# photon_v019.net
KiCad netlist of a schematic drawn in EAGLE
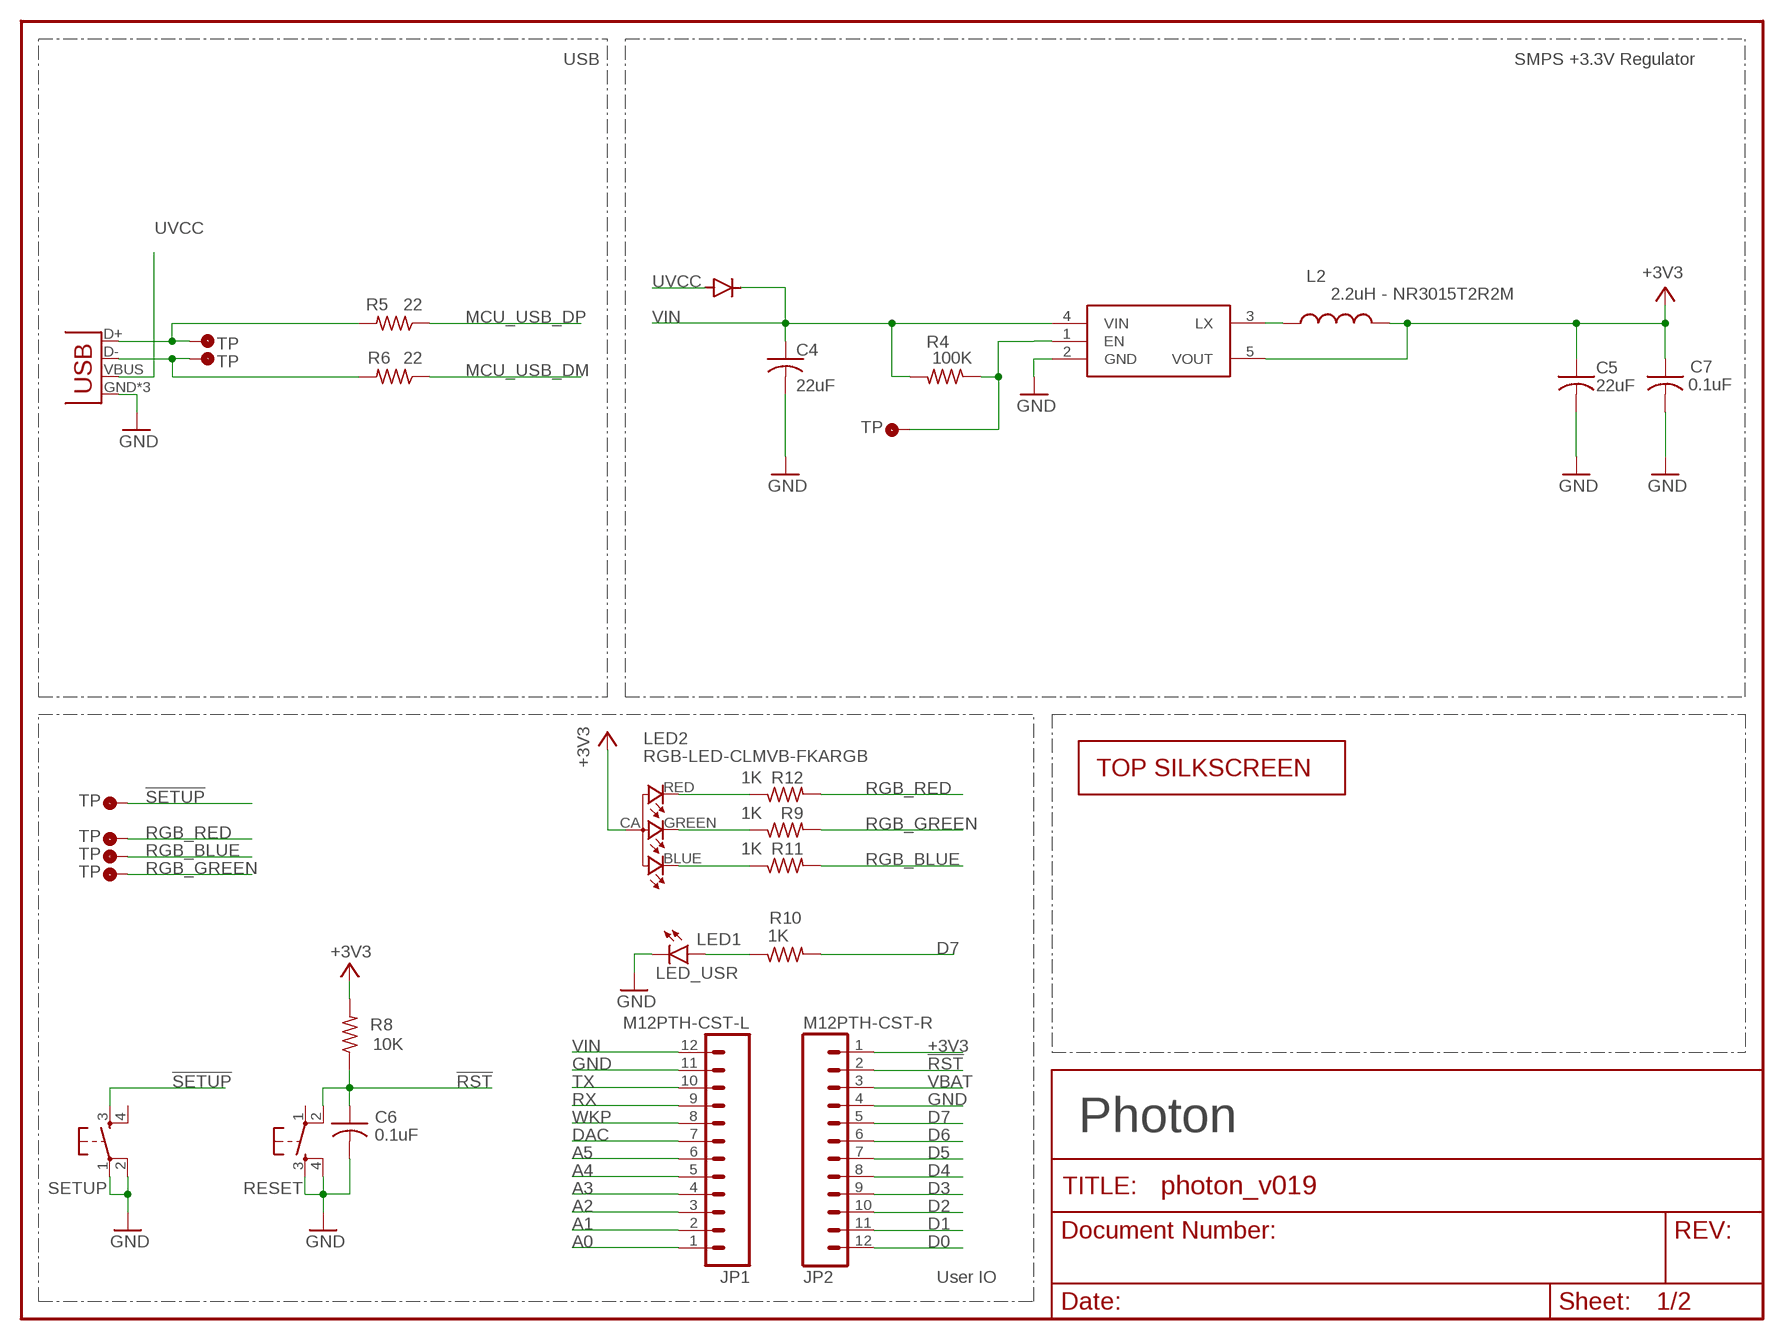
[diagram p0: schematic, sheet 1]
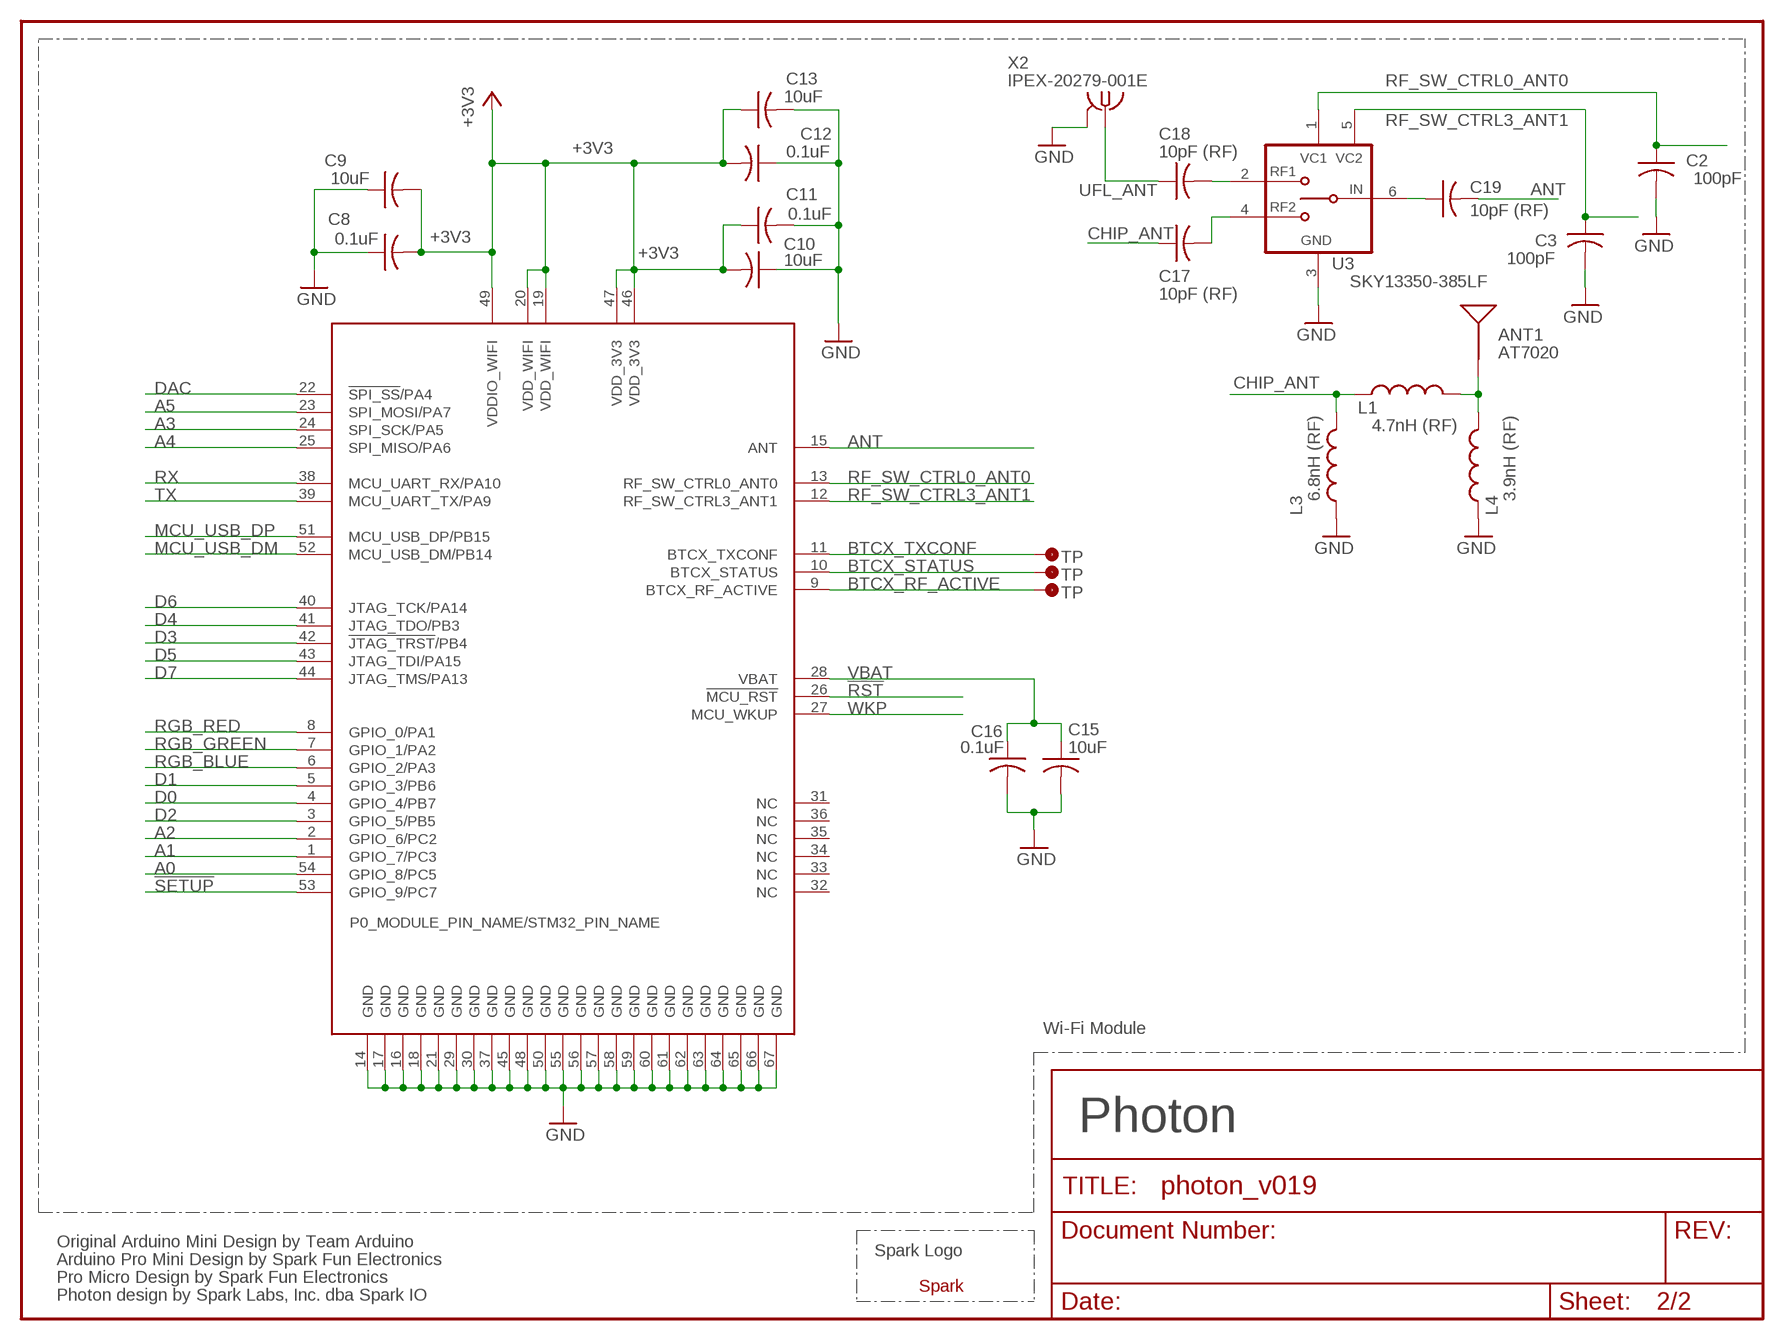
[diagram p1: schematic, sheet 2]

(export (version "E")
  (design (tool "Eeschema 10.0.6"))
  (components
    (comp (ref "C4")
      (value "22uF")
      (footprint "eagle-import:C0603_B")
      (libsource (lib "eagle-import") (part "C-US0603"))
    )
    (comp (ref "C5")
      (value "22uF")
      (footprint "eagle-import:C0603_B")
      (libsource (lib "eagle-import") (part "C-US0603"))
    )
    (comp (ref "C6")
      (value "0.1uF")
      (footprint "eagle-import:C0402_B")
      (libsource (lib "eagle-import") (part "C-US"))
    )
    (comp (ref "C7")
      (value "0.1uF")
      (footprint "eagle-import:C0402_B")
      (libsource (lib "eagle-import") (part "C-US"))
    )
    (comp (ref "D1")
      (value "DIODE")
      (footprint "eagle-import:DIODE-DO-220AA(SMP)")
      (libsource (lib "eagle-import") (part "DIODE"))
    )
    (comp (ref "JP1")
      (value "M12PTH-CST-L")
      (footprint "eagle-import:1X12-CASTELLATED")
      (libsource (lib "eagle-import") (part "M12PTH-CST-L"))
    )
    (comp (ref "JP2")
      (value "M12PTH-CST-R")
      (footprint "eagle-import:1X12-CASTELLATED")
      (libsource (lib "eagle-import") (part "M12PTH-CST-R"))
    )
    (comp (ref "L2")
      (value "2.2uH - NR3015T2R2M")
      (footprint "eagle-import:INDUCTOR-NR3015")
      (libsource (lib "eagle-import") (part "INDUCTORB"))
    )
    (comp (ref "LED2")
      (value "RGB-LED-CLMVB-FKARGB")
      (footprint "eagle-import:PLCC4-2MM-RGB")
      (libsource (lib "eagle-import") (part "RGB-LED-CLMVB-FKARGB"))
    )
    (comp (ref "LED_USR")
      (value "LED-0603-NO-SS")
      (footprint "eagle-import:LED-0603-NO-SS")
      (libsource (lib "eagle-import") (part "LED-0603-NO-SS"))
    )
    (comp (ref "R4")
      (value "100K")
      (footprint "eagle-import:R0402_B")
      (libsource (lib "eagle-import") (part "R-US_"))
    )
    (comp (ref "R5")
      (value "22")
      (footprint "eagle-import:R0402_B")
      (libsource (lib "eagle-import") (part "R-US_"))
    )
    (comp (ref "R6")
      (value "22")
      (footprint "eagle-import:R0402_B")
      (libsource (lib "eagle-import") (part "R-US_"))
    )
    (comp (ref "R8")
      (value "10K")
      (footprint "eagle-import:R0402_B")
      (libsource (lib "eagle-import") (part "R-US_"))
    )
    (comp (ref "R9")
      (value "1K")
      (footprint "eagle-import:R0402_B")
      (libsource (lib "eagle-import") (part "R-US_"))
    )
    (comp (ref "R10")
      (value "1K")
      (footprint "eagle-import:R0402_B")
      (libsource (lib "eagle-import") (part "R-US_"))
    )
    (comp (ref "R11")
      (value "1K")
      (footprint "eagle-import:R0402_B")
      (libsource (lib "eagle-import") (part "R-US_"))
    )
    (comp (ref "R12")
      (value "1K")
      (footprint "eagle-import:R0402_B")
      (libsource (lib "eagle-import") (part "R-US_"))
    )
    (comp (ref "RESET")
      (value "KMR211GLFS")
      (footprint "eagle-import:TACTILE_SWITCH_SMD")
      (libsource (lib "eagle-import") (part "TAC_SWITCHSMD"))
    )
    (comp (ref "SETUP")
      (value "KMR211GLFS")
      (footprint "eagle-import:TACTILE_SWITCH_SMD")
      (libsource (lib "eagle-import") (part "TAC_SWITCHSMD"))
    )
    (comp (ref "U$1")
      (value "PHOTON-TOP-SS2")
      (footprint "eagle-import:PHOTON-TOP-SS-2")
      (libsource (lib "eagle-import") (part "PHOTON-TOP-SS2"))
    )
    (comp (ref "U$3")
      (value "TP3")
      (footprint "eagle-import:TP60_BOT")
      (libsource (lib "eagle-import") (part "TP3"))
    )
    (comp (ref "U$5")
      (value "TP1")
      (footprint "eagle-import:TP35_BOT")
      (libsource (lib "eagle-import") (part "TP1"))
    )
    (comp (ref "U$6")
      (value "TP1")
      (footprint "eagle-import:TP35_BOT")
      (libsource (lib "eagle-import") (part "TP1"))
    )
    (comp (ref "U$7")
      (value "TP1")
      (footprint "eagle-import:TP35_BOT")
      (libsource (lib "eagle-import") (part "TP1"))
    )
    (comp (ref "U$11")
      (value "R8008-33")
      (footprint "eagle-import:SOT23-5")
      (libsource (lib "eagle-import") (part "R8008-33"))
    )
    (comp (ref "U$12")
      (value "TP3")
      (footprint "eagle-import:TP60_BOT")
      (libsource (lib "eagle-import") (part "TP3"))
    )
    (comp (ref "U$13")
      (value "TP3")
      (footprint "eagle-import:TP60_BOT")
      (libsource (lib "eagle-import") (part "TP3"))
    )
    (comp (ref "U$14")
      (value "TP3")
      (footprint "eagle-import:TP60_BOT")
      (libsource (lib "eagle-import") (part "TP3"))
    )
    (comp (ref "X1")
      (value "USB-MICROB")
      (footprint "eagle-import:USB-MICROB-SLOT-HOLE")
      (libsource (lib "eagle-import") (part "USBUSB-MICROB-SLOT-HOLE"))
    )
    (comp (ref "ANT1")
      (value "AT7020")
      (footprint "eagle-import:AT7020")
      (libsource (lib "eagle-import") (part "AT7020"))
    )
    (comp (ref "C2")
      (value "100pF")
      (footprint "eagle-import:C0402_B")
      (libsource (lib "eagle-import") (part "C-US"))
    )
    (comp (ref "C3")
      (value "100pF")
      (footprint "eagle-import:C0402_B")
      (libsource (lib "eagle-import") (part "C-US"))
    )
    (comp (ref "C8")
      (value "0.1uF")
      (footprint "eagle-import:C0402_B")
      (libsource (lib "eagle-import") (part "C-US"))
    )
    (comp (ref "C9")
      (value "10uF")
      (footprint "eagle-import:C0603_B")
      (libsource (lib "eagle-import") (part "C-US0603"))
    )
    (comp (ref "C10")
      (value "10uF")
      (footprint "eagle-import:C0603_B")
      (libsource (lib "eagle-import") (part "C-US0603"))
    )
    (comp (ref "C11")
      (value "0.1uF")
      (footprint "eagle-import:C0402_B")
      (libsource (lib "eagle-import") (part "C-US"))
    )
    (comp (ref "C12")
      (value "0.1uF")
      (footprint "eagle-import:C0402_B")
      (libsource (lib "eagle-import") (part "C-US"))
    )
    (comp (ref "C13")
      (value "10uF")
      (footprint "eagle-import:C0603_B")
      (libsource (lib "eagle-import") (part "C-US0603"))
    )
    (comp (ref "C15")
      (value "10uF")
      (footprint "eagle-import:C0603_B")
      (libsource (lib "eagle-import") (part "C-US0603"))
    )
    (comp (ref "C16")
      (value "0.1uF")
      (footprint "eagle-import:C0402_B")
      (libsource (lib "eagle-import") (part "C-US"))
    )
    (comp (ref "C17")
      (value "10pF (RF)")
      (footprint "eagle-import:C0201_B")
      (libsource (lib "eagle-import") (part "C-US0201"))
    )
    (comp (ref "C18")
      (value "10pF (RF)")
      (footprint "eagle-import:C0201_B")
      (libsource (lib "eagle-import") (part "C-US0201"))
    )
    (comp (ref "C19")
      (value "10pF (RF)")
      (footprint "eagle-import:C0201_B")
      (libsource (lib "eagle-import") (part "C-US0201"))
    )
    (comp (ref "L1")
      (value "4.7nH (RF)")
      (footprint "eagle-import:L0402_B")
      (libsource (lib "eagle-import") (part "INDUCTOR"))
    )
    (comp (ref "L3")
      (value "6.8nH (RF)")
      (footprint "eagle-import:L0402_B")
      (libsource (lib "eagle-import") (part "INDUCTOR"))
    )
    (comp (ref "L4")
      (value "3.9nH (RF)")
      (footprint "eagle-import:L0402_B")
      (libsource (lib "eagle-import") (part "INDUCTOR"))
    )
    (comp (ref "U$2")
      (value "SPARK_LOGO2")
      (footprint "eagle-import:SPARK_LOGO2")
      (libsource (lib "eagle-import") (part "SPARK_LOGO2"))
    )
    (comp (ref "U$8")
      (value "TP1")
      (footprint "eagle-import:TP35_BOT")
      (libsource (lib "eagle-import") (part "TP1"))
    )
    (comp (ref "U$9")
      (value "TP1")
      (footprint "eagle-import:TP35_BOT")
      (libsource (lib "eagle-import") (part "TP1"))
    )
    (comp (ref "U$10")
      (value "TP1")
      (footprint "eagle-import:TP35_BOT")
      (libsource (lib "eagle-import") (part "TP1"))
    )
    (comp (ref "U1")
      (value "WM-N-BM-09")
      (footprint "eagle-import:WM-N-BM-09")
      (libsource (lib "eagle-import") (part "WM-N-BM-09"))
    )
    (comp (ref "U3")
      (value "SKY13350-385LF")
      (footprint "eagle-import:XFDFN-6")
      (libsource (lib "eagle-import") (part "SKY13350-385LF"))
    )
    (comp (ref "X2")
      (value "IPEX-20279-001E")
      (footprint "eagle-import:IPEX-20279-001E")
      (libsource (lib "eagle-import") (part "IPEX-20279-001E"))
    )
  )
  (nets
    (net (code "1") (name "+3V3") (class "Default")
      (node (ref "C10") (pin "2") (pinfunction "2_2") (pintype "passive"))
      (node (ref "C11") (pin "1") (pinfunction "1_1") (pintype "passive"))
      (node (ref "C12") (pin "2") (pinfunction "2_2") (pintype "passive"))
      (node (ref "C13") (pin "1") (pinfunction "1_1") (pintype "passive"))
      (node (ref "C5") (pin "1") (pinfunction "1_1") (pintype "passive"))
      (node (ref "C7") (pin "1") (pinfunction "1_1") (pintype "passive"))
      (node (ref "C8") (pin "2") (pinfunction "2_2") (pintype "passive"))
      (node (ref "C9") (pin "2") (pinfunction "2_2") (pintype "passive"))
      (node (ref "JP2") (pin "1") (pinfunction "1_1") (pintype "passive"))
      (node (ref "L2") (pin "2") (pinfunction "2_2") (pintype "passive"))
      (node (ref "LED2") (pin "CA") (pinfunction "1_CA") (pintype "passive"))
      (node (ref "R8") (pin "2") (pinfunction "2_2") (pintype "passive"))
      (node (ref "U$11") (pin "5") (pinfunction "VOUT_5") (pintype "bidirectional"))
      (node (ref "U1") (pin "19") (pinfunction "VDD_WIFI_19") (pintype "bidirectional"))
      (node (ref "U1") (pin "20") (pinfunction "VDD_WIFI_20") (pintype "bidirectional"))
      (node (ref "U1") (pin "46") (pinfunction "VDD_3V3_46") (pintype "bidirectional"))
      (node (ref "U1") (pin "47") (pinfunction "VDD_3V3_47") (pintype "bidirectional"))
      (node (ref "U1") (pin "49") (pinfunction "VDDIO_WIFI_49") (pintype "bidirectional"))
    )
    (net (code "2") (name "A0") (class "Default")
      (node (ref "JP1") (pin "1") (pinfunction "12_1") (pintype "passive"))
      (node (ref "U1") (pin "54") (pinfunction "GPIO_8/PC5_54") (pintype "bidirectional"))
    )
    (net (code "3") (name "A1") (class "Default")
      (node (ref "JP1") (pin "2") (pinfunction "11_2") (pintype "passive"))
      (node (ref "U1") (pin "1") (pinfunction "GPIO_7/PC3_1") (pintype "bidirectional"))
    )
    (net (code "4") (name "A2") (class "Default")
      (node (ref "JP1") (pin "3") (pinfunction "10_3") (pintype "passive"))
      (node (ref "U1") (pin "2") (pinfunction "GPIO_6/PC2_2") (pintype "bidirectional"))
    )
    (net (code "5") (name "A3") (class "Default")
      (node (ref "JP1") (pin "4") (pinfunction "9_4") (pintype "passive"))
      (node (ref "U1") (pin "24") (pinfunction "SPI_SCK/PA5_24") (pintype "bidirectional"))
    )
    (net (code "6") (name "A4") (class "Default")
      (node (ref "JP1") (pin "5") (pinfunction "8_5") (pintype "passive"))
      (node (ref "U1") (pin "25") (pinfunction "SPI_MISO/PA6_25") (pintype "bidirectional"))
    )
    (net (code "7") (name "A5") (class "Default")
      (node (ref "JP1") (pin "6") (pinfunction "7_6") (pintype "passive"))
      (node (ref "U1") (pin "23") (pinfunction "SPI_MOSI/PA7_23") (pintype "bidirectional"))
    )
    (net (code "8") (name "ANT") (class "Default")
      (node (ref "C19") (pin "2") (pinfunction "2_2") (pintype "passive"))
      (node (ref "U1") (pin "15") (pinfunction "ANT_15") (pintype "bidirectional"))
    )
    (net (code "9") (name "BTCX_RF_ACTIVE") (class "Default")
      (node (ref "U$10") (pin "P$1") (pinfunction "TP_P$1") (pintype "bidirectional"))
      (node (ref "U1") (pin "9") (pinfunction "BTCX_RF_ACTIVE_9") (pintype "bidirectional"))
    )
    (net (code "10") (name "BTCX_STATUS") (class "Default")
      (node (ref "U$9") (pin "P$1") (pinfunction "TP_P$1") (pintype "bidirectional"))
      (node (ref "U1") (pin "10") (pinfunction "BTCX_STATUS_10") (pintype "bidirectional"))
    )
    (net (code "11") (name "BTCX_TXCONF") (class "Default")
      (node (ref "U$8") (pin "P$1") (pinfunction "TP_P$1") (pintype "bidirectional"))
      (node (ref "U1") (pin "11") (pinfunction "BTCX_TXCONF_11") (pintype "bidirectional"))
    )
    (net (code "12") (name "CHIP_ANT") (class "Default")
      (node (ref "C17") (pin "1") (pinfunction "1_1") (pintype "passive"))
      (node (ref "L1") (pin "1") (pinfunction "1_1") (pintype "passive"))
      (node (ref "L3") (pin "2") (pinfunction "2_2") (pintype "passive"))
    )
    (net (code "13") (name "D0") (class "Default")
      (node (ref "JP2") (pin "12") (pinfunction "12_12") (pintype "passive"))
      (node (ref "U1") (pin "4") (pinfunction "GPIO_4/PB7_4") (pintype "bidirectional"))
    )
    (net (code "14") (name "D1") (class "Default")
      (node (ref "JP2") (pin "11") (pinfunction "11_11") (pintype "passive"))
      (node (ref "U1") (pin "5") (pinfunction "GPIO_3/PB6_5") (pintype "bidirectional"))
    )
    (net (code "15") (name "D2") (class "Default")
      (node (ref "JP2") (pin "10") (pinfunction "10_10") (pintype "passive"))
      (node (ref "U1") (pin "3") (pinfunction "GPIO_5/PB5_3") (pintype "bidirectional"))
    )
    (net (code "16") (name "D3") (class "Default")
      (node (ref "JP2") (pin "9") (pinfunction "9_9") (pintype "passive"))
      (node (ref "U1") (pin "42") (pinfunction "~{JTAG_TRST}/PB4_42") (pintype "bidirectional"))
    )
    (net (code "17") (name "D4") (class "Default")
      (node (ref "JP2") (pin "8") (pinfunction "8_8") (pintype "passive"))
      (node (ref "U1") (pin "41") (pinfunction "JTAG_TDO/PB3_41") (pintype "bidirectional"))
    )
    (net (code "18") (name "D5") (class "Default")
      (node (ref "JP2") (pin "7") (pinfunction "7_7") (pintype "passive"))
      (node (ref "U1") (pin "43") (pinfunction "JTAG_TDI/PA15_43") (pintype "bidirectional"))
    )
    (net (code "19") (name "D6") (class "Default")
      (node (ref "JP2") (pin "6") (pinfunction "6_6") (pintype "passive"))
      (node (ref "U1") (pin "40") (pinfunction "JTAG_TCK/PA14_40") (pintype "bidirectional"))
    )
    (net (code "20") (name "D7") (class "Default")
      (node (ref "JP2") (pin "5") (pinfunction "5_5") (pintype "passive"))
      (node (ref "R10") (pin "2") (pinfunction "2_2") (pintype "passive"))
      (node (ref "U1") (pin "44") (pinfunction "JTAG_TMS/PA13_44") (pintype "bidirectional"))
    )
    (net (code "21") (name "DAC") (class "Default")
      (node (ref "JP1") (pin "7") (pinfunction "6_7") (pintype "passive"))
      (node (ref "U1") (pin "22") (pinfunction "~{SPI_SS}/PA4_22") (pintype "bidirectional"))
    )
    (net (code "22") (name "GND") (class "Default")
      (node (ref "C10") (pin "1") (pinfunction "1_1") (pintype "passive"))
      (node (ref "C11") (pin "2") (pinfunction "2_2") (pintype "passive"))
      (node (ref "C12") (pin "1") (pinfunction "1_1") (pintype "passive"))
      (node (ref "C13") (pin "2") (pinfunction "2_2") (pintype "passive"))
      (node (ref "C15") (pin "2") (pinfunction "2_2") (pintype "passive"))
      (node (ref "C16") (pin "2") (pinfunction "2_2") (pintype "passive"))
      (node (ref "C2") (pin "2") (pinfunction "2_2") (pintype "passive"))
      (node (ref "C3") (pin "2") (pinfunction "2_2") (pintype "passive"))
      (node (ref "C4") (pin "2") (pinfunction "2_2") (pintype "passive"))
      (node (ref "C5") (pin "2") (pinfunction "2_2") (pintype "passive"))
      (node (ref "C6") (pin "2") (pinfunction "2_2") (pintype "passive"))
      (node (ref "C7") (pin "2") (pinfunction "2_2") (pintype "passive"))
      (node (ref "C8") (pin "1") (pinfunction "1_1") (pintype "passive"))
      (node (ref "C9") (pin "1") (pinfunction "1_1") (pintype "passive"))
      (node (ref "JP1") (pin "11") (pinfunction "2_11") (pintype "passive"))
      (node (ref "JP2") (pin "4") (pinfunction "4_4") (pintype "passive"))
      (node (ref "L3") (pin "1") (pinfunction "1_1") (pintype "passive"))
      (node (ref "L4") (pin "1") (pinfunction "1_1") (pintype "passive"))
      (node (ref "LED_USR") (pin "C1") (pinfunction "C_C1") (pintype "passive"))
      (node (ref "RESET") (pin "3") (pinfunction "3_3") (pintype "passive"))
      (node (ref "RESET") (pin "4") (pinfunction "4_4") (pintype "passive"))
      (node (ref "SETUP") (pin "1") (pinfunction "1_1") (pintype "passive"))
      (node (ref "SETUP") (pin "2") (pinfunction "2_2") (pintype "passive"))
      (node (ref "U$11") (pin "2") (pinfunction "GND_2") (pintype "bidirectional"))
      (node (ref "U1") (pin "14") (pinfunction "GND_14") (pintype "bidirectional"))
      (node (ref "U1") (pin "16") (pinfunction "GND_16") (pintype "bidirectional"))
      (node (ref "U1") (pin "17") (pinfunction "GND_17") (pintype "bidirectional"))
      (node (ref "U1") (pin "18") (pinfunction "GND_18") (pintype "bidirectional"))
      (node (ref "U1") (pin "21") (pinfunction "GND_21") (pintype "bidirectional"))
      (node (ref "U1") (pin "29") (pinfunction "GND_29") (pintype "bidirectional"))
      (node (ref "U1") (pin "30") (pinfunction "GND_30") (pintype "bidirectional"))
      (node (ref "U1") (pin "37") (pinfunction "GND_37") (pintype "bidirectional"))
      (node (ref "U1") (pin "45") (pinfunction "GND_45") (pintype "bidirectional"))
      (node (ref "U1") (pin "48") (pinfunction "GND_48") (pintype "bidirectional"))
      (node (ref "U1") (pin "50") (pinfunction "GND_50") (pintype "bidirectional"))
      (node (ref "U1") (pin "55") (pinfunction "GND_55") (pintype "bidirectional"))
      (node (ref "U1") (pin "56") (pinfunction "GND_56") (pintype "bidirectional"))
      (node (ref "U1") (pin "57") (pinfunction "GND_57") (pintype "bidirectional"))
      (node (ref "U1") (pin "58") (pinfunction "GND_58") (pintype "bidirectional"))
      (node (ref "U1") (pin "59") (pinfunction "GND_59") (pintype "bidirectional"))
      (node (ref "U1") (pin "60") (pinfunction "GND_60") (pintype "bidirectional"))
      (node (ref "U1") (pin "61") (pinfunction "GND_61") (pintype "bidirectional"))
      (node (ref "U1") (pin "62") (pinfunction "GND_62") (pintype "bidirectional"))
      (node (ref "U1") (pin "63") (pinfunction "GND_63") (pintype "bidirectional"))
      (node (ref "U1") (pin "64") (pinfunction "GND_64") (pintype "bidirectional"))
      (node (ref "U1") (pin "65") (pinfunction "GND_65") (pintype "bidirectional"))
      (node (ref "U1") (pin "66") (pinfunction "GND_66") (pintype "bidirectional"))
      (node (ref "U1") (pin "67") (pinfunction "GND_67") (pintype "bidirectional"))
      (node (ref "U3") (pin "3") (pinfunction "GND_3") (pintype "power_in"))
      (node (ref "X1") (pin "GND") (pinfunction "GND_GND") (pintype "bidirectional"))
      (node (ref "X1") (pin "MT1") (pinfunction "GND_MT1") (pintype "bidirectional"))
      (node (ref "X1") (pin "MT2") (pinfunction "GND_MT2") (pintype "bidirectional"))
      (node (ref "X2") (pin "2@1") (pinfunction "GND_2@1") (pintype "passive"))
      (node (ref "X2") (pin "2@2") (pinfunction "GND_2@2") (pintype "passive"))
    )
    (net (code "23") (name "LED1") (class "Default")
      (node (ref "LED_USR") (pin "A1") (pinfunction "A_A1") (pintype "passive"))
      (node (ref "R10") (pin "1") (pinfunction "1_1") (pintype "passive"))
    )
    (net (code "24") (name "MCU_USB_DM") (class "Default")
      (node (ref "R6") (pin "1") (pinfunction "1_1") (pintype "passive"))
      (node (ref "U1") (pin "52") (pinfunction "MCU_USB_DM/PB14_52") (pintype "bidirectional"))
    )
    (net (code "25") (name "MCU_USB_DP") (class "Default")
      (node (ref "R5") (pin "1") (pinfunction "1_1") (pintype "passive"))
      (node (ref "U1") (pin "51") (pinfunction "MCU_USB_DP/PB15_51") (pintype "bidirectional"))
    )
    (net (code "26") (name "Net-(ANT1-SIGNAL)") (class "Default")
      (node (ref "ANT1") (pin "1") (pinfunction "SIGNAL_1") (pintype "bidirectional"))
      (node (ref "L1") (pin "2") (pinfunction "2_2") (pintype "passive"))
      (node (ref "L4") (pin "2") (pinfunction "2_2") (pintype "passive"))
    )
    (net (code "27") (name "Net-(LED2-2)") (class "Default")
      (node (ref "LED2") (pin "BLUE") (pinfunction "2_BLUE") (pintype "passive"))
      (node (ref "R11") (pin "1") (pinfunction "1_1") (pintype "passive"))
    )
    (net (code "28") (name "Net-(LED2-3)") (class "Default")
      (node (ref "LED2") (pin "GREEN") (pinfunction "3_GREEN") (pintype "passive"))
      (node (ref "R9") (pin "1") (pinfunction "1_1") (pintype "passive"))
    )
    (net (code "29") (name "Net-(LED2-4)") (class "Default")
      (node (ref "LED2") (pin "RED") (pinfunction "4_RED") (pintype "passive"))
      (node (ref "R12") (pin "1") (pinfunction "1_1") (pintype "passive"))
    )
    (net (code "30") (name "Net-(U$11-EN)") (class "Default")
      (node (ref "R4") (pin "1") (pinfunction "1_1") (pintype "passive"))
      (node (ref "U$11") (pin "1") (pinfunction "EN_1") (pintype "bidirectional"))
      (node (ref "U$12") (pin "P$1") (pinfunction "TP_P$1") (pintype "bidirectional"))
    )
    (net (code "31") (name "Net-(U$11-LX)") (class "Default")
      (node (ref "L2") (pin "1") (pinfunction "1_1") (pintype "passive"))
      (node (ref "U$11") (pin "3") (pinfunction "LX_3") (pintype "bidirectional"))
    )
    (net (code "32") (name "Net-(U$13-TP)") (class "Default")
      (node (ref "R5") (pin "2") (pinfunction "2_2") (pintype "passive"))
      (node (ref "U$13") (pin "P$1") (pinfunction "TP_P$1") (pintype "bidirectional"))
      (node (ref "X1") (pin "D+") (pinfunction "D+_D+") (pintype "bidirectional"))
    )
    (net (code "33") (name "Net-(U$14-TP)") (class "Default")
      (node (ref "R6") (pin "2") (pinfunction "2_2") (pintype "passive"))
      (node (ref "U$14") (pin "P$1") (pinfunction "TP_P$1") (pintype "bidirectional"))
      (node (ref "X1") (pin "D-") (pinfunction "D-_D-") (pintype "bidirectional"))
    )
    (net (code "34") (name "Net-(U3B-IN)") (class "Default")
      (node (ref "C19") (pin "1") (pinfunction "1_1") (pintype "passive"))
      (node (ref "U3") (pin "6") (pinfunction "IN_6") (pintype "bidirectional"))
    )
    (net (code "35") (name "Net-(U3B-RF1)") (class "Default")
      (node (ref "C18") (pin "2") (pinfunction "2_2") (pintype "passive"))
      (node (ref "U3") (pin "2") (pinfunction "RF1_2") (pintype "bidirectional"))
    )
    (net (code "36") (name "Net-(U3B-RF2)") (class "Default")
      (node (ref "C17") (pin "2") (pinfunction "2_2") (pintype "passive"))
      (node (ref "U3") (pin "4") (pinfunction "RF2_4") (pintype "bidirectional"))
    )
    (net (code "37") (name "RF_SW_CTRL0_ANT0") (class "Default")
      (node (ref "C2") (pin "1") (pinfunction "1_1") (pintype "passive"))
      (node (ref "U1") (pin "13") (pinfunction "RF_SW_CTRL0_ANT0_13") (pintype "bidirectional"))
      (node (ref "U3") (pin "1") (pinfunction "VC1_1") (pintype "input"))
    )
    (net (code "38") (name "RF_SW_CTRL3_ANT1") (class "Default")
      (node (ref "C3") (pin "1") (pinfunction "1_1") (pintype "passive"))
      (node (ref "U1") (pin "12") (pinfunction "RF_SW_CTRL3_ANT1_12") (pintype "bidirectional"))
      (node (ref "U3") (pin "5") (pinfunction "VC2_5") (pintype "input"))
    )
    (net (code "39") (name "RGB_BLUE") (class "Default")
      (node (ref "R11") (pin "2") (pinfunction "2_2") (pintype "passive"))
      (node (ref "U$6") (pin "P$1") (pinfunction "TP_P$1") (pintype "bidirectional"))
      (node (ref "U1") (pin "6") (pinfunction "GPIO_2/PA3_6") (pintype "bidirectional"))
    )
    (net (code "40") (name "RGB_GREEN") (class "Default")
      (node (ref "R9") (pin "2") (pinfunction "2_2") (pintype "passive"))
      (node (ref "U$7") (pin "P$1") (pinfunction "TP_P$1") (pintype "bidirectional"))
      (node (ref "U1") (pin "7") (pinfunction "GPIO_1/PA2_7") (pintype "bidirectional"))
    )
    (net (code "41") (name "RGB_RED") (class "Default")
      (node (ref "R12") (pin "2") (pinfunction "2_2") (pintype "passive"))
      (node (ref "U$5") (pin "P$1") (pinfunction "TP_P$1") (pintype "bidirectional"))
      (node (ref "U1") (pin "8") (pinfunction "GPIO_0/PA1_8") (pintype "bidirectional"))
    )
    (net (code "42") (name "RX") (class "Default")
      (node (ref "JP1") (pin "9") (pinfunction "4_9") (pintype "passive"))
      (node (ref "U1") (pin "38") (pinfunction "MCU_UART_RX/PA10_38") (pintype "bidirectional"))
    )
    (net (code "43") (name "TX") (class "Default")
      (node (ref "JP1") (pin "10") (pinfunction "3_10") (pintype "passive"))
      (node (ref "U1") (pin "39") (pinfunction "MCU_UART_TX/PA9_39") (pintype "bidirectional"))
    )
    (net (code "44") (name "UFL_ANT") (class "Default")
      (node (ref "C18") (pin "1") (pinfunction "1_1") (pintype "passive"))
      (node (ref "X2") (pin "1") (pinfunction "1_1") (pintype "passive"))
    )
    (net (code "45") (name "UVCC") (class "Default")
      (node (ref "D1") (pin "ANODE") (pinfunction "ANODE_ANODE") (pintype "bidirectional"))
      (node (ref "X1") (pin "VBUS") (pinfunction "VBUS_VBUS") (pintype "bidirectional"))
    )
    (net (code "46") (name "VBAT") (class "Default")
      (node (ref "C15") (pin "1") (pinfunction "1_1") (pintype "passive"))
      (node (ref "C16") (pin "1") (pinfunction "1_1") (pintype "passive"))
      (node (ref "JP2") (pin "3") (pinfunction "3_3") (pintype "passive"))
      (node (ref "U1") (pin "28") (pinfunction "VBAT_28") (pintype "bidirectional"))
    )
    (net (code "47") (name "VIN") (class "Default")
      (node (ref "C4") (pin "1") (pinfunction "1_1") (pintype "passive"))
      (node (ref "D1") (pin "CATHODE") (pinfunction "CATHODE_CATHODE") (pintype "bidirectional"))
      (node (ref "JP1") (pin "12") (pinfunction "1_12") (pintype "passive"))
      (node (ref "R4") (pin "2") (pinfunction "2_2") (pintype "passive"))
      (node (ref "U$11") (pin "4") (pinfunction "VIN_4") (pintype "bidirectional"))
    )
    (net (code "48") (name "WKP") (class "Default")
      (node (ref "JP1") (pin "8") (pinfunction "5_8") (pintype "passive"))
      (node (ref "U1") (pin "27") (pinfunction "MCU_WKUP_27") (pintype "bidirectional"))
    )
    (net (code "49") (name "unconnected-(RESET-Pad1)") (class "Default")
      (node (ref "RESET") (pin "1") (pinfunction "1_1") (pintype "passive"))
    )
    (net (code "50") (name "unconnected-(SETUP-Pad4)") (class "Default")
      (node (ref "SETUP") (pin "4") (pinfunction "4_4") (pintype "passive"))
    )
    (net (code "51") (name "unconnected-(U1-NC-Pad31)") (class "Default")
      (node (ref "U1") (pin "31") (pinfunction "NC_31") (pintype "bidirectional"))
    )
    (net (code "52") (name "unconnected-(U1-NC-Pad32)") (class "Default")
      (node (ref "U1") (pin "32") (pinfunction "NC_32") (pintype "bidirectional"))
    )
    (net (code "53") (name "unconnected-(U1-NC-Pad33)") (class "Default")
      (node (ref "U1") (pin "33") (pinfunction "NC_33") (pintype "bidirectional"))
    )
    (net (code "54") (name "unconnected-(U1-NC-Pad34)") (class "Default")
      (node (ref "U1") (pin "34") (pinfunction "NC_34") (pintype "bidirectional"))
    )
    (net (code "55") (name "unconnected-(U1-NC-Pad35)") (class "Default")
      (node (ref "U1") (pin "35") (pinfunction "NC_35") (pintype "bidirectional"))
    )
    (net (code "56") (name "unconnected-(U1-NC-Pad36)") (class "Default")
      (node (ref "U1") (pin "36") (pinfunction "NC_36") (pintype "bidirectional"))
    )
    (net (code "57") (name "~{RST}") (class "Default")
      (node (ref "C6") (pin "1") (pinfunction "1_1") (pintype "passive"))
      (node (ref "JP2") (pin "2") (pinfunction "2_2") (pintype "passive"))
      (node (ref "R8") (pin "1") (pinfunction "1_1") (pintype "passive"))
      (node (ref "RESET") (pin "2") (pinfunction "2_2") (pintype "passive"))
      (node (ref "U1") (pin "26") (pinfunction "~{MCU_RST}_26") (pintype "bidirectional"))
    )
    (net (code "58") (name "~{SETUP}") (class "Default")
      (node (ref "SETUP") (pin "3") (pinfunction "3_3") (pintype "passive"))
      (node (ref "U$3") (pin "P$1") (pinfunction "TP_P$1") (pintype "bidirectional"))
      (node (ref "U1") (pin "53") (pinfunction "GPIO_9/PC7_53") (pintype "bidirectional"))
    )
  )
)
